# shinobi_motor.net
KiCad netlist of a schematic drawn in EAGLE
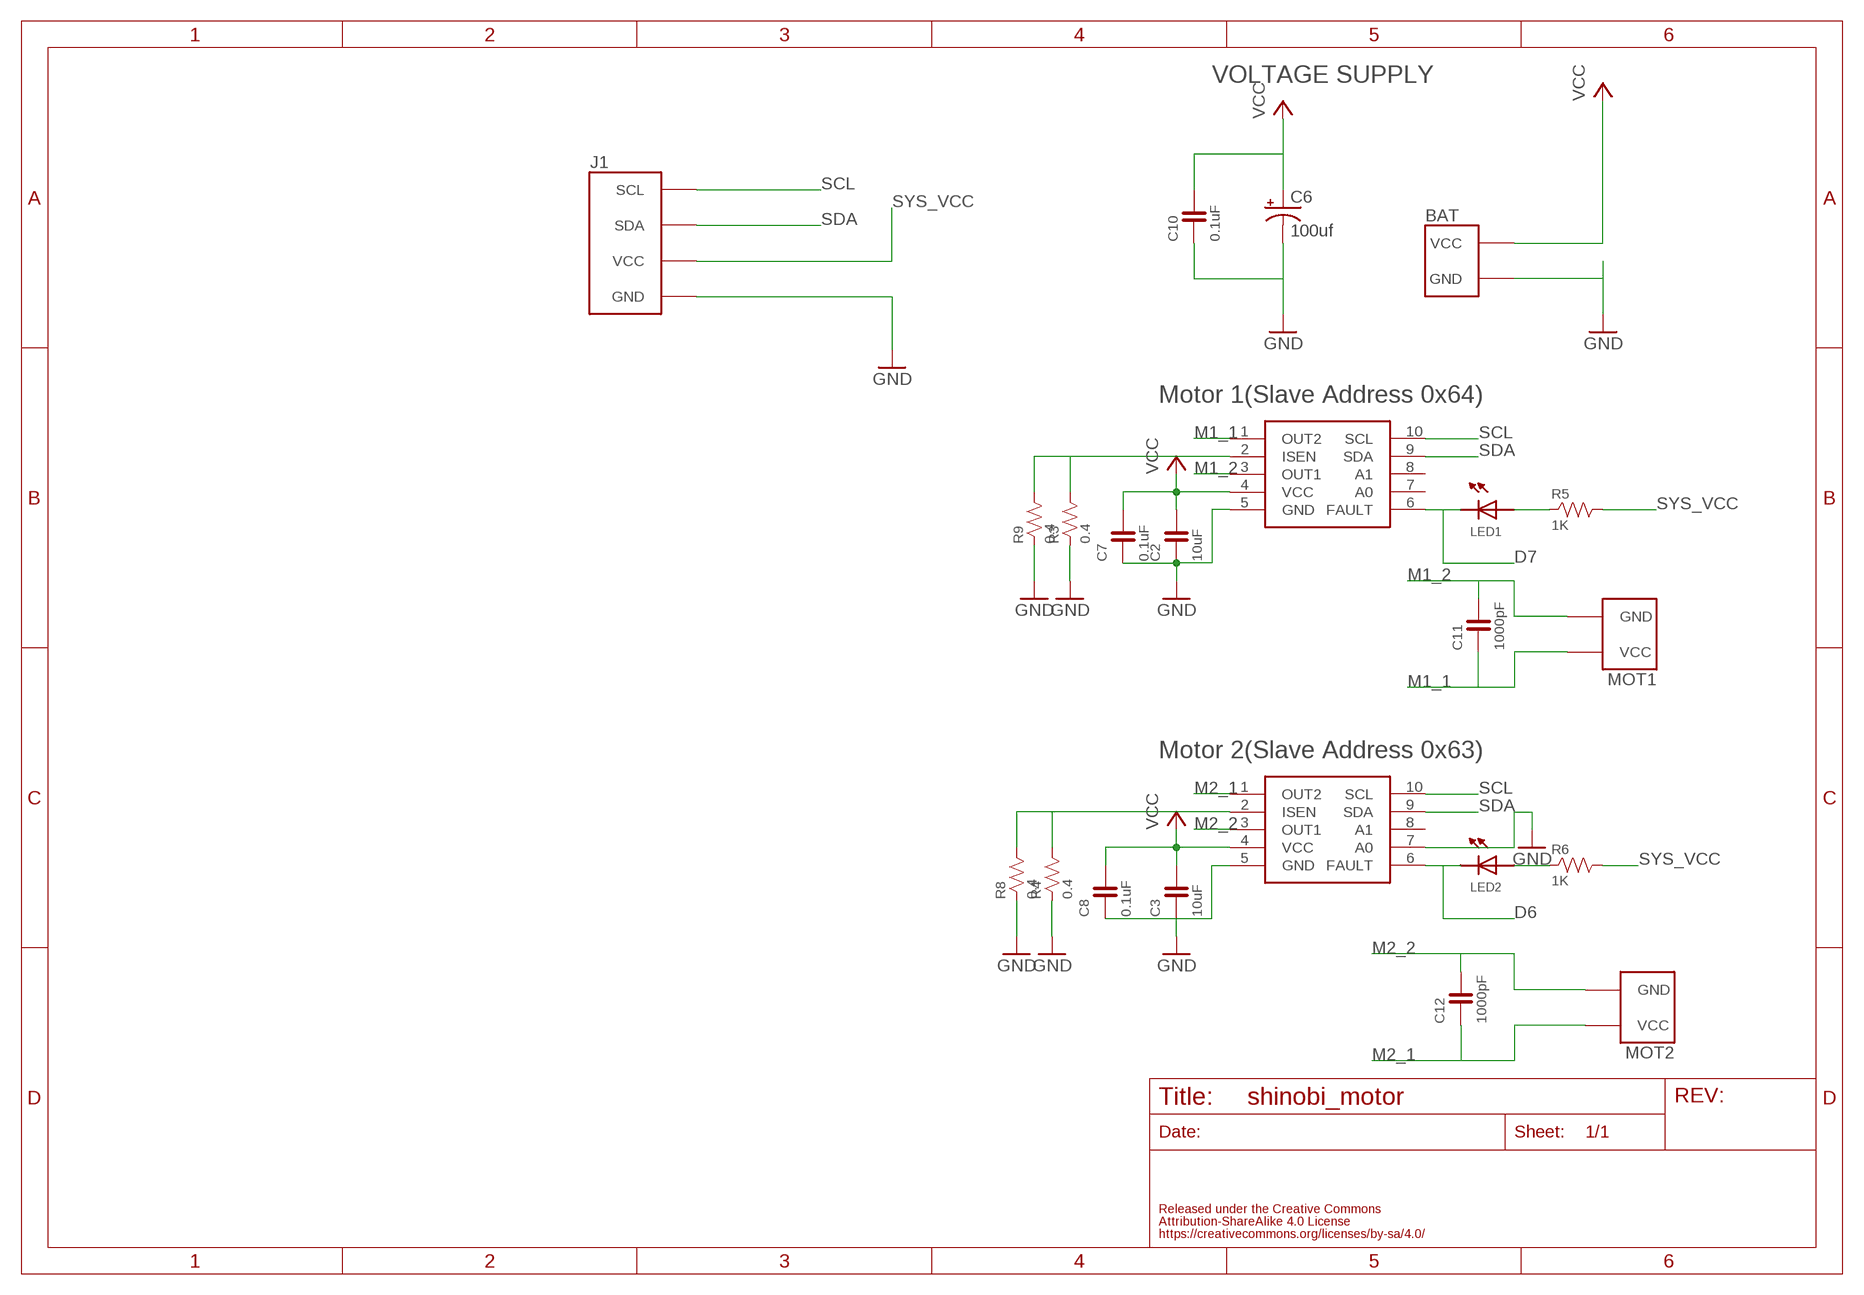
[diagram p0: schematic, sheet 1]

(export (version "E")
  (design (tool "Eeschema 10.0.6"))
  (components
    (comp (ref "BAT")
      (value "FABO_BRICK_2PIN_SIDE")
      (footprint "eagle-import:FABO_BRICK_2PIN_S02B−PASK-2_SILK")
      (libsource (lib "eagle-import") (part "FABO_BRICK_2PIN_SIDE"))
    )
    (comp (ref "C2")
      (value "10uF")
      (footprint "eagle-import:0603")
      (libsource (lib "eagle-import") (part "CAPACITOR-0603"))
    )
    (comp (ref "C3")
      (value "10uF")
      (footprint "eagle-import:0603")
      (libsource (lib "eagle-import") (part "CAPACITOR-0603"))
    )
    (comp (ref "C6")
      (value "100uf")
      (footprint "eagle-import:153CLV-0405")
      (libsource (lib "eagle-import") (part "CPOL-US153CLV-0405"))
    )
    (comp (ref "C7")
      (value "0.1uF")
      (footprint "eagle-import:0603")
      (libsource (lib "eagle-import") (part "CAPACITOR-0603"))
    )
    (comp (ref "C8")
      (value "0.1uF")
      (footprint "eagle-import:0603")
      (libsource (lib "eagle-import") (part "CAPACITOR-0603"))
    )
    (comp (ref "C10")
      (value "0.1uF")
      (footprint "eagle-import:0603")
      (libsource (lib "eagle-import") (part "CAPACITOR-0603"))
    )
    (comp (ref "C11")
      (value "1000pF")
      (footprint "eagle-import:0603")
      (libsource (lib "eagle-import") (part "CAPACITOR-0603"))
    )
    (comp (ref "C12")
      (value "1000pF")
      (footprint "eagle-import:0603")
      (libsource (lib "eagle-import") (part "CAPACITOR-0603"))
    )
    (comp (ref "J1")
      (value "FABO_BRICK_I2C-S04B-PASK-2_LONG")
      (footprint "eagle-import:FABO_BRICK_I2C_S04B-PASK-2_LONG")
      (libsource (lib "eagle-import") (part "FABO_BRICK_I2C-S04B-PASK-2_LONG"))
    )
    (comp (ref "LED1")
      (value "LED-0603")
      (footprint "eagle-import:0603")
      (libsource (lib "eagle-import") (part "LED-0603"))
    )
    (comp (ref "LED2")
      (value "LED-0603")
      (footprint "eagle-import:0603")
      (libsource (lib "eagle-import") (part "LED-0603"))
    )
    (comp (ref "MOT1")
      (value "FABO_BRICK_2PIN_SIDE")
      (footprint "eagle-import:FABO_BRICK_2PIN_S02B−PASK-2_SILK")
      (libsource (lib "eagle-import") (part "FABO_BRICK_2PIN_SIDE"))
    )
    (comp (ref "MOT2")
      (value "FABO_BRICK_2PIN_SIDE")
      (footprint "eagle-import:FABO_BRICK_2PIN_S02B−PASK-2_SILK")
      (libsource (lib "eagle-import") (part "FABO_BRICK_2PIN_SIDE"))
    )
    (comp (ref "R3")
      (value "0.4")
      (footprint "eagle-import:0603")
      (libsource (lib "eagle-import") (part "RESISTOR-0603"))
    )
    (comp (ref "R4")
      (value "0.4")
      (footprint "eagle-import:0603")
      (libsource (lib "eagle-import") (part "RESISTOR-0603"))
    )
    (comp (ref "R5")
      (value "1K")
      (footprint "eagle-import:0603")
      (libsource (lib "eagle-import") (part "RESISTOR-0603"))
    )
    (comp (ref "R6")
      (value "1K")
      (footprint "eagle-import:0603")
      (libsource (lib "eagle-import") (part "RESISTOR-0603"))
    )
    (comp (ref "R8")
      (value "0.4")
      (footprint "eagle-import:0603")
      (libsource (lib "eagle-import") (part "RESISTOR-0603"))
    )
    (comp (ref "R9")
      (value "0.4")
      (footprint "eagle-import:0603")
      (libsource (lib "eagle-import") (part "RESISTOR-0603"))
    )
    (comp (ref "U$8")
      (value "DRV8830")
      (footprint "eagle-import:DRV8830")
      (libsource (lib "eagle-import") (part "DRV8830"))
    )
    (comp (ref "U$10")
      (value "DRV8830")
      (footprint "eagle-import:DRV8830")
      (libsource (lib "eagle-import") (part "DRV8830"))
    )
  )
  (nets
    (net (code "1") (name "/D6") (class "Default")
      (node (ref "LED2") (pin "CATHODE") (pinfunction "CATHODE_CATHODE") (pintype "passive"))
      (node (ref "U$10") (pin "6") (pinfunction "FAULT_6") (pintype "bidirectional"))
    )
    (net (code "2") (name "/D7") (class "Default")
      (node (ref "LED1") (pin "CATHODE") (pinfunction "CATHODE_CATHODE") (pintype "passive"))
      (node (ref "U$8") (pin "6") (pinfunction "FAULT_6") (pintype "bidirectional"))
    )
    (net (code "3") (name "/M1_1") (class "Default")
      (node (ref "C11") (pin "1") (pinfunction "1_1") (pintype "passive"))
      (node (ref "MOT1") (pin "VCC") (pinfunction "VCC_VCC") (pintype "bidirectional"))
      (node (ref "U$8") (pin "1") (pinfunction "OUT2_1") (pintype "bidirectional"))
    )
    (net (code "4") (name "/M1_2") (class "Default")
      (node (ref "C11") (pin "2") (pinfunction "2_2") (pintype "passive"))
      (node (ref "MOT1") (pin "GND") (pinfunction "GND_GND") (pintype "bidirectional"))
      (node (ref "U$8") (pin "3") (pinfunction "OUT1_3") (pintype "bidirectional"))
    )
    (net (code "5") (name "/M2_1") (class "Default")
      (node (ref "C12") (pin "1") (pinfunction "1_1") (pintype "passive"))
      (node (ref "MOT2") (pin "VCC") (pinfunction "VCC_VCC") (pintype "bidirectional"))
      (node (ref "U$10") (pin "1") (pinfunction "OUT2_1") (pintype "bidirectional"))
    )
    (net (code "6") (name "/M2_2") (class "Default")
      (node (ref "C12") (pin "2") (pinfunction "2_2") (pintype "passive"))
      (node (ref "MOT2") (pin "GND") (pinfunction "GND_GND") (pintype "bidirectional"))
      (node (ref "U$10") (pin "3") (pinfunction "OUT1_3") (pintype "bidirectional"))
    )
    (net (code "7") (name "/SCL") (class "Default")
      (node (ref "J1") (pin "SCL") (pinfunction "SCL_SCL") (pintype "bidirectional"))
      (node (ref "U$10") (pin "10") (pinfunction "SCL_10") (pintype "bidirectional"))
      (node (ref "U$8") (pin "10") (pinfunction "SCL_10") (pintype "bidirectional"))
    )
    (net (code "8") (name "/SDA") (class "Default")
      (node (ref "J1") (pin "SDA") (pinfunction "SDA_SDA") (pintype "bidirectional"))
      (node (ref "U$10") (pin "9") (pinfunction "SDA_9") (pintype "bidirectional"))
      (node (ref "U$8") (pin "9") (pinfunction "SDA_9") (pintype "bidirectional"))
    )
    (net (code "9") (name "/SYS_VCC") (class "Default")
      (node (ref "J1") (pin "VCC") (pinfunction "VCC_VCC") (pintype "bidirectional"))
      (node (ref "R5") (pin "2") (pinfunction "2_2") (pintype "bidirectional"))
      (node (ref "R6") (pin "2") (pinfunction "2_2") (pintype "bidirectional"))
    )
    (net (code "10") (name "GND") (class "Default")
      (node (ref "BAT") (pin "GND") (pinfunction "GND_GND") (pintype "bidirectional"))
      (node (ref "C10") (pin "1") (pinfunction "1_1") (pintype "passive"))
      (node (ref "C2") (pin "1") (pinfunction "1_1") (pintype "passive"))
      (node (ref "C3") (pin "1") (pinfunction "1_1") (pintype "passive"))
      (node (ref "C6") (pin "-") (pinfunction "-_-") (pintype "passive"))
      (node (ref "C7") (pin "1") (pinfunction "1_1") (pintype "passive"))
      (node (ref "C8") (pin "1") (pinfunction "1_1") (pintype "passive"))
      (node (ref "J1") (pin "GND") (pinfunction "GND_GND") (pintype "bidirectional"))
      (node (ref "R3") (pin "1") (pinfunction "1_1") (pintype "bidirectional"))
      (node (ref "R4") (pin "1") (pinfunction "1_1") (pintype "bidirectional"))
      (node (ref "R8") (pin "1") (pinfunction "1_1") (pintype "bidirectional"))
      (node (ref "R9") (pin "1") (pinfunction "1_1") (pintype "bidirectional"))
      (node (ref "U$10") (pin "5") (pinfunction "GND_5") (pintype "bidirectional"))
      (node (ref "U$10") (pin "7") (pinfunction "A0_7") (pintype "bidirectional"))
      (node (ref "U$8") (pin "5") (pinfunction "GND_5") (pintype "bidirectional"))
    )
    (net (code "11") (name "Net-(LED1-PadANODE)") (class "Default")
      (node (ref "LED1") (pin "ANODE") (pinfunction "ANODE_ANODE") (pintype "passive"))
      (node (ref "R5") (pin "1") (pinfunction "1_1") (pintype "bidirectional"))
    )
    (net (code "12") (name "Net-(LED2-PadANODE)") (class "Default")
      (node (ref "LED2") (pin "ANODE") (pinfunction "ANODE_ANODE") (pintype "passive"))
      (node (ref "R6") (pin "1") (pinfunction "1_1") (pintype "bidirectional"))
    )
    (net (code "13") (name "Net-(U$8-ISEN)") (class "Default")
      (node (ref "R3") (pin "2") (pinfunction "2_2") (pintype "bidirectional"))
      (node (ref "R9") (pin "2") (pinfunction "2_2") (pintype "bidirectional"))
      (node (ref "U$8") (pin "2") (pinfunction "ISEN_2") (pintype "bidirectional"))
    )
    (net (code "14") (name "Net-(U$10-ISEN)") (class "Default")
      (node (ref "R4") (pin "2") (pinfunction "2_2") (pintype "bidirectional"))
      (node (ref "R8") (pin "2") (pinfunction "2_2") (pintype "bidirectional"))
      (node (ref "U$10") (pin "2") (pinfunction "ISEN_2") (pintype "bidirectional"))
    )
    (net (code "15") (name "VCC") (class "Default")
      (node (ref "BAT") (pin "VCC") (pinfunction "VCC_VCC") (pintype "bidirectional"))
      (node (ref "C10") (pin "2") (pinfunction "2_2") (pintype "passive"))
      (node (ref "C2") (pin "2") (pinfunction "2_2") (pintype "passive"))
      (node (ref "C3") (pin "2") (pinfunction "2_2") (pintype "passive"))
      (node (ref "C6") (pin "+") (pinfunction "+_+") (pintype "passive"))
      (node (ref "C7") (pin "2") (pinfunction "2_2") (pintype "passive"))
      (node (ref "C8") (pin "2") (pinfunction "2_2") (pintype "passive"))
      (node (ref "U$10") (pin "4") (pinfunction "VCC_4") (pintype "bidirectional"))
      (node (ref "U$8") (pin "4") (pinfunction "VCC_4") (pintype "bidirectional"))
    )
    (net (code "16") (name "unconnected-(U$8-A0-Pad7)") (class "Default")
      (node (ref "U$8") (pin "7") (pinfunction "A0_7") (pintype "bidirectional"))
    )
    (net (code "17") (name "unconnected-(U$8-A1-Pad8)") (class "Default")
      (node (ref "U$8") (pin "8") (pinfunction "A1_8") (pintype "bidirectional"))
    )
    (net (code "18") (name "unconnected-(U$10-A1-Pad8)") (class "Default")
      (node (ref "U$10") (pin "8") (pinfunction "A1_8") (pintype "bidirectional"))
    )
  )
)
